# power.net
KiCad netlist of a schematic drawn in Altium Designer
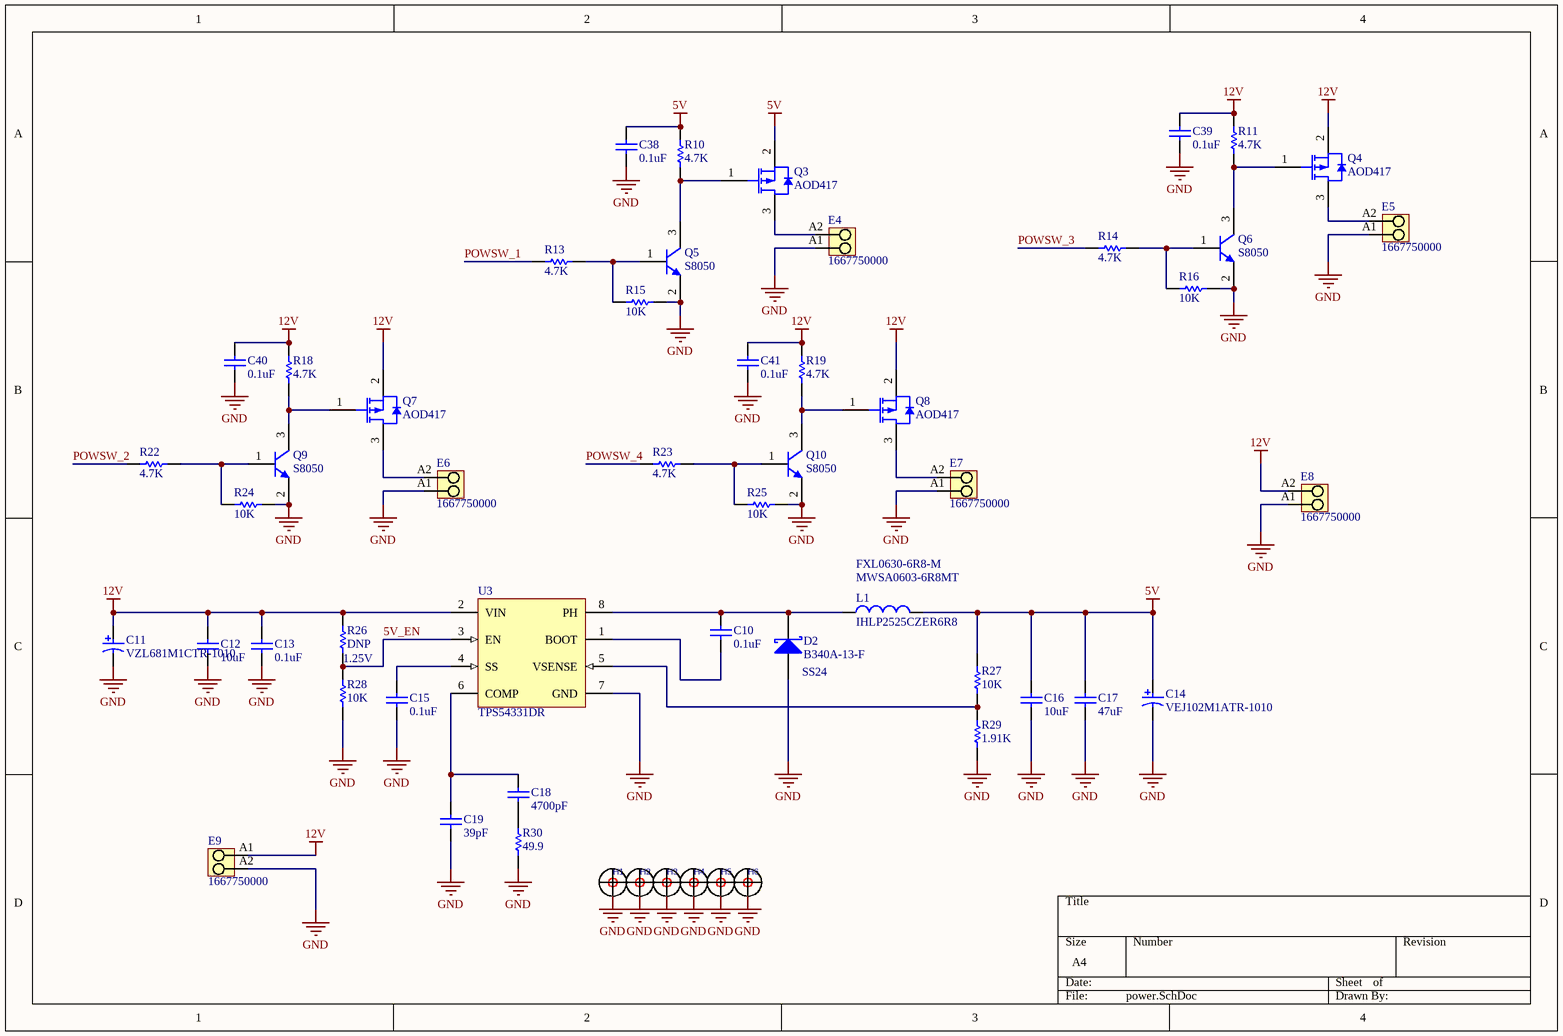
[diagram p0: power.SchDoc]

(export (version "E")
  (design (tool "Eeschema 10.0.6"))
  (components
    (comp (ref "C10")
      (value "0.1uF")
      (footprint "CAPC0603(1608)100_L")
      (description "0603 (1608 Metric) Chip Capacitor")
      (libsource (lib "Altium Content Vault") (part "CAP_5"))
    )
    (comp (ref "C11")
      (value "VZL681M1CTR-1010")
      (footprint "PNSC-SVP-F12_L")
      (description "680uF,16V,-55~105℃")
      (fields (field (name "TOLERANCE") "±20%") (field (name "MANUFACTURER") "Lelon"))
      (libsource (lib "Altium Content Vault") (part "CAP-P-2"))
    )
    (comp (ref "C12")
      (value "10uF")
      (footprint "CAPC0805(2012)145_L")
      (description "0805 (2012 Metric) Chip Capacitor")
      (libsource (lib "PCB_Project1") (part "CAP_5_1"))
    )
    (comp (ref "C13")
      (value "0.1uF")
      (footprint "CAPC0603(1608)100_L")
      (description "0603 (1608 Metric) Chip Capacitor")
      (libsource (lib "Altium Content Vault") (part "CAP_5"))
    )
    (comp (ref "C14")
      (value "VEJ102M1ATR-1010")
      (footprint "PNSC-SVP-F12_L")
      (description "1000uF,10V,-55~105℃")
      (fields (field (name "TOLERANCE") "±20%") (field (name "MANUFACTURER") "Lelon"))
      (libsource (lib "Altium Content Vault") (part "CAP-P-2"))
    )
    (comp (ref "C15")
      (value "0.1uF")
      (footprint "CAPC0603(1608)100_L")
      (description "0603 (1608 Metric) Chip Capacitor")
      (libsource (lib "Altium Content Vault") (part "CAP_5"))
    )
    (comp (ref "C16")
      (value "10uF")
      (footprint "CAPC0805(2012)145_L")
      (description "0805 (2012 Metric) Chip Capacitor")
      (libsource (lib "PCB_Project1") (part "CAP_5_1"))
    )
    (comp (ref "C17")
      (value "47uF")
      (footprint "CAPC1206(3216)150_L")
      (description "1206 (3216 Metric) Chip Capacitor")
      (libsource (lib "IC0") (part "CAP_5_3"))
    )
    (comp (ref "C18")
      (value "4700pF")
      (footprint "CAPC0603(1608)100_L")
      (description "0603 (1608 Metric) Chip Capacitor")
      (libsource (lib "Altium Content Vault") (part "CAP_5"))
    )
    (comp (ref "C19")
      (value "39pF")
      (footprint "CAPC0603(1608)100_L")
      (description "0603 (1608 Metric) Chip Capacitor")
      (libsource (lib "Altium Content Vault") (part "CAP_5"))
    )
    (comp (ref "C38")
      (value "0.1uF")
      (footprint "CAPC0603(1608)100_L")
      (description "0603 (1608 Metric) Chip Capacitor")
      (libsource (lib "Altium Content Vault") (part "CAP_5"))
    )
    (comp (ref "C39")
      (value "0.1uF")
      (footprint "CAPC0603(1608)100_L")
      (description "0603 (1608 Metric) Chip Capacitor")
      (libsource (lib "Altium Content Vault") (part "CAP_5"))
    )
    (comp (ref "C40")
      (value "0.1uF")
      (footprint "CAPC0603(1608)100_L")
      (description "0603 (1608 Metric) Chip Capacitor")
      (libsource (lib "Altium Content Vault") (part "CAP_5"))
    )
    (comp (ref "C41")
      (value "0.1uF")
      (footprint "CAPC0603(1608)100_L")
      (description "0603 (1608 Metric) Chip Capacitor")
      (libsource (lib "Altium Content Vault") (part "CAP_5"))
    )
    (comp (ref "D2")
      (value "B340A-13-F")
      (footprint "DIOD-SMA-2_V")
      (libsource (lib "Altium Content Vault") (part "DSKY-AK-2"))
    )
    (comp (ref "E4")
      (value "1667750000")
      (footprint "LM_3_5_90_02")
      (description "OMNIMATE Signal - series LM")
      (fields (field (name "MANUFACTURER") "Weidmueller"))
      (libsource (lib "Altium Content Vault") (part "Terminal_02_1x02"))
    )
    (comp (ref "E5")
      (value "1667750000")
      (footprint "LM_3_5_90_02")
      (description "OMNIMATE Signal - series LM")
      (fields (field (name "MANUFACTURER") "Weidmueller"))
      (libsource (lib "Altium Content Vault") (part "Terminal_02_1x02"))
    )
    (comp (ref "E6")
      (value "1667750000")
      (footprint "LM_3_5_90_02")
      (description "OMNIMATE Signal - series LM")
      (fields (field (name "MANUFACTURER") "Weidmueller"))
      (libsource (lib "Altium Content Vault") (part "Terminal_02_1x02"))
    )
    (comp (ref "E7")
      (value "1667750000")
      (footprint "LM_3_5_90_02")
      (description "OMNIMATE Signal - series LM")
      (fields (field (name "MANUFACTURER") "Weidmueller"))
      (libsource (lib "Altium Content Vault") (part "Terminal_02_1x02"))
    )
    (comp (ref "E8")
      (value "1667750000")
      (footprint "LM_3_5_90_02")
      (description "OMNIMATE Signal - series LM")
      (fields (field (name "MANUFACTURER") "Weidmueller"))
      (libsource (lib "Altium Content Vault") (part "Terminal_02_1x02"))
    )
    (comp (ref "E9")
      (value "1667750000")
      (footprint "LM_3_5_90_02")
      (description "OMNIMATE Signal - series LM")
      (fields (field (name "MANUFACTURER") "Weidmueller"))
      (libsource (lib "") (part "Terminal_02_1x02_1"))
    )
    (comp (ref "H1") (value "HOLE") (footprint "HOLE_Φ3_3") (libsource (lib "小车") (part "HOLE")))
    (comp (ref "H2") (value "HOLE") (footprint "HOLE_Φ3_3") (libsource (lib "小车") (part "HOLE")))
    (comp (ref "H3") (value "HOLE") (footprint "HOLE_Φ3_3") (libsource (lib "小车") (part "HOLE")))
    (comp (ref "H4") (value "HOLE") (footprint "HOLE_Φ3_3") (libsource (lib "小车") (part "HOLE")))
    (comp (ref "H5") (value "HOLE") (footprint "HOLE_Φ3_3") (libsource (lib "小车") (part "HOLE")))
    (comp (ref "H6") (value "HOLE") (footprint "HOLE_Φ3_3") (libsource (lib "小车") (part "HOLE")))
    (comp (ref "L1")
      (value "IHLP2525CZER6R8")
      (footprint "VISH-IHLP2525CZER220M11_V")
      (fields (field (name "MANUFACTURER") "Vishay") (field (name "TOLERANCE") "±20%"))
      (libsource (lib "Altium Content Vault") (part "IND-2"))
    )
    (comp (ref "Q3")
      (value "AOD417")
      (footprint "DIOD-TO252-3_V")
      (fields (field (name "MANUFACTURER") "Diodes Inc"))
      (libsource (lib "Altium Content Vault") (part "PEMOS-GSD-3"))
    )
    (comp (ref "Q4")
      (value "AOD417")
      (footprint "DIOD-TO252-3_V")
      (fields (field (name "MANUFACTURER") "Diodes Inc"))
      (libsource (lib "Altium Content Vault") (part "PEMOS-GSD-3"))
    )
    (comp (ref "Q5")
      (value "S8050")
      (footprint "KOCN-SOT23-3_L")
      (description "NPN Transistor, 0.8 A Collector Current, 3-Pin SOT23, RoHS, Tape and Reel")
      (fields (field (name "MANUFACTURER") "Koo Chin"))
      (libsource (lib "Altium Content Vault") (part "KOCN-NPN-B1E2C3-3"))
    )
    (comp (ref "Q6")
      (value "S8050")
      (footprint "KOCN-SOT23-3_L")
      (description "NPN Transistor, 0.8 A Collector Current, 3-Pin SOT23, RoHS, Tape and Reel")
      (fields (field (name "MANUFACTURER") "Koo Chin"))
      (libsource (lib "Altium Content Vault") (part "KOCN-NPN-B1E2C3-3"))
    )
    (comp (ref "Q7")
      (value "AOD417")
      (footprint "DIOD-TO252-3_V")
      (fields (field (name "MANUFACTURER") "Diodes Inc"))
      (libsource (lib "Altium Content Vault") (part "PEMOS-GSD-3"))
    )
    (comp (ref "Q8")
      (value "AOD417")
      (footprint "DIOD-TO252-3_V")
      (fields (field (name "MANUFACTURER") "Diodes Inc"))
      (libsource (lib "Altium Content Vault") (part "PEMOS-GSD-3"))
    )
    (comp (ref "Q9")
      (value "S8050")
      (footprint "KOCN-SOT23-3_L")
      (description "NPN Transistor, 0.8 A Collector Current, 3-Pin SOT23, RoHS, Tape and Reel")
      (fields (field (name "MANUFACTURER") "Koo Chin"))
      (libsource (lib "Altium Content Vault") (part "KOCN-NPN-B1E2C3-3"))
    )
    (comp (ref "Q10")
      (value "S8050")
      (footprint "KOCN-SOT23-3_L")
      (description "NPN Transistor, 0.8 A Collector Current, 3-Pin SOT23, RoHS, Tape and Reel")
      (fields (field (name "MANUFACTURER") "Koo Chin"))
      (libsource (lib "Altium Content Vault") (part "KOCN-NPN-B1E2C3-3"))
    )
    (comp (ref "R10")
      (value "4.7K")
      (footprint "RESC0603(1608)_L")
      (description "0603 (1608 Metric) Chip Resistor")
      (libsource (lib "PCB_Project1") (part "RES_3_1"))
    )
    (comp (ref "R11")
      (value "4.7K")
      (footprint "RESC0603(1608)_L")
      (description "0603 (1608 Metric) Chip Resistor")
      (libsource (lib "PCB_Project1") (part "RES_3_1"))
    )
    (comp (ref "R13")
      (value "4.7K")
      (footprint "RESC0603(1608)_L")
      (description "0603 (1608 Metric) Chip Resistor")
      (libsource (lib "PCB_Project1") (part "RES_3_1"))
    )
    (comp (ref "R14")
      (value "4.7K")
      (footprint "RESC0603(1608)_L")
      (description "0603 (1608 Metric) Chip Resistor")
      (libsource (lib "PCB_Project1") (part "RES_3_1"))
    )
    (comp (ref "R15")
      (value "10K")
      (footprint "RESC0603(1608)_L")
      (description "0603 (1608 Metric) Chip Resistor")
      (libsource (lib "PCB_Project1") (part "RES_3_1"))
    )
    (comp (ref "R16")
      (value "10K")
      (footprint "RESC0603(1608)_L")
      (description "0603 (1608 Metric) Chip Resistor")
      (libsource (lib "PCB_Project1") (part "RES_3_1"))
    )
    (comp (ref "R18")
      (value "4.7K")
      (footprint "RESC0603(1608)_L")
      (description "0603 (1608 Metric) Chip Resistor")
      (libsource (lib "PCB_Project1") (part "RES_3_1"))
    )
    (comp (ref "R19")
      (value "4.7K")
      (footprint "RESC0603(1608)_L")
      (description "0603 (1608 Metric) Chip Resistor")
      (libsource (lib "PCB_Project1") (part "RES_3_1"))
    )
    (comp (ref "R22")
      (value "4.7K")
      (footprint "RESC0603(1608)_L")
      (description "0603 (1608 Metric) Chip Resistor")
      (libsource (lib "PCB_Project1") (part "RES_3_1"))
    )
    (comp (ref "R23")
      (value "4.7K")
      (footprint "RESC0603(1608)_L")
      (description "0603 (1608 Metric) Chip Resistor")
      (libsource (lib "PCB_Project1") (part "RES_3_1"))
    )
    (comp (ref "R24")
      (value "10K")
      (footprint "RESC0603(1608)_L")
      (description "0603 (1608 Metric) Chip Resistor")
      (libsource (lib "PCB_Project1") (part "RES_3_1"))
    )
    (comp (ref "R25")
      (value "10K")
      (footprint "RESC0603(1608)_L")
      (description "0603 (1608 Metric) Chip Resistor")
      (libsource (lib "PCB_Project1") (part "RES_3_1"))
    )
    (comp (ref "R26")
      (value "DNP")
      (footprint "RESC0603(1608)_L")
      (description "0603 (1608 Metric) Chip Resistor")
      (libsource (lib "PCB_Project1") (part "RES_3_1"))
    )
    (comp (ref "R27")
      (value "10K")
      (footprint "RESC0603(1608)_L")
      (description "0603 (1608 Metric) Chip Resistor")
      (libsource (lib "PCB_Project1") (part "RES_3_1"))
    )
    (comp (ref "R28")
      (value "10K")
      (footprint "RESC0603(1608)_L")
      (description "0603 (1608 Metric) Chip Resistor")
      (libsource (lib "PCB_Project1") (part "RES_3_1"))
    )
    (comp (ref "R29")
      (value "1.91K")
      (footprint "RESC0603(1608)_L")
      (description "0603 (1608 Metric) Chip Resistor")
      (libsource (lib "PCB_Project1") (part "RES_3_1"))
    )
    (comp (ref "R30")
      (value "49.9")
      (footprint "RESC0603(1608)_L")
      (description "0603 (1608 Metric) Chip Resistor")
      (libsource (lib "PCB_Project1") (part "RES_3_1"))
    )
    (comp (ref "U3")
      (value "TPS54331DR")
      (footprint "D8_N")
      (fields (field (name "MANUFACTURER") "Texas Instruments"))
      (libsource (lib "Altium Content Vault") (part "TI-TPS54331D8"))
    )
  )
  (nets
    (net (code "1") (name "/5V_EN") (class "Default")
      (node (ref "R26") (pin "2") (pinfunction "2_2") (pintype "passive"))
      (node (ref "R28") (pin "1") (pinfunction "1_1") (pintype "passive"))
      (node (ref "U3") (pin "3") (pinfunction "EN_3") (pintype "input"))
    )
    (net (code "2") (name "/POWSW_1") (class "Default")
      (node (ref "R13") (pin "1") (pinfunction "1_1") (pintype "passive"))
    )
    (net (code "3") (name "/POWSW_2") (class "Default")
      (node (ref "R22") (pin "1") (pinfunction "1_1") (pintype "passive"))
    )
    (net (code "4") (name "/POWSW_3") (class "Default")
      (node (ref "R14") (pin "1") (pinfunction "1_1") (pintype "passive"))
    )
    (net (code "5") (name "/POWSW_4") (class "Default")
      (node (ref "R23") (pin "1") (pinfunction "1_1") (pintype "passive"))
    )
    (net (code "6") (name "5V") (class "Default")
      (node (ref "C14") (pin "1") (pinfunction "1_1") (pintype "passive"))
      (node (ref "C16") (pin "2") (pinfunction "2_2") (pintype "passive"))
      (node (ref "C17") (pin "2") (pinfunction "2_2") (pintype "passive"))
      (node (ref "C38") (pin "2") (pinfunction "2_2") (pintype "passive"))
      (node (ref "L1") (pin "2") (pinfunction "2_2") (pintype "passive"))
      (node (ref "Q3") (pin "2") (pinfunction "SOURCE_2") (pintype "passive"))
      (node (ref "R10") (pin "1") (pinfunction "1_1") (pintype "passive"))
      (node (ref "R27") (pin "1") (pinfunction "1_1") (pintype "passive"))
    )
    (net (code "7") (name "12V") (class "Default")
      (node (ref "C11") (pin "1") (pinfunction "1_1") (pintype "passive"))
      (node (ref "C12") (pin "2") (pinfunction "2_2") (pintype "passive"))
      (node (ref "C13") (pin "2") (pinfunction "2_2") (pintype "passive"))
      (node (ref "C39") (pin "2") (pinfunction "2_2") (pintype "passive"))
      (node (ref "C40") (pin "2") (pinfunction "2_2") (pintype "passive"))
      (node (ref "C41") (pin "2") (pinfunction "2_2") (pintype "passive"))
      (node (ref "E8") (pin "A2") (pinfunction "A2_A2") (pintype "passive"))
      (node (ref "E9") (pin "A1") (pinfunction "A1_A1") (pintype "passive"))
      (node (ref "Q4") (pin "2") (pinfunction "SOURCE_2") (pintype "passive"))
      (node (ref "Q7") (pin "2") (pinfunction "SOURCE_2") (pintype "passive"))
      (node (ref "Q8") (pin "2") (pinfunction "SOURCE_2") (pintype "passive"))
      (node (ref "R11") (pin "1") (pinfunction "1_1") (pintype "passive"))
      (node (ref "R18") (pin "1") (pinfunction "1_1") (pintype "passive"))
      (node (ref "R19") (pin "1") (pinfunction "1_1") (pintype "passive"))
      (node (ref "R26") (pin "1") (pinfunction "1_1") (pintype "passive"))
      (node (ref "U3") (pin "2") (pinfunction "VIN_2") (pintype "power_in"))
    )
    (net (code "8") (name "GND") (class "Default")
      (node (ref "C11") (pin "2") (pinfunction "2_2") (pintype "passive"))
      (node (ref "C12") (pin "1") (pinfunction "1_1") (pintype "passive"))
      (node (ref "C13") (pin "1") (pinfunction "1_1") (pintype "passive"))
      (node (ref "C14") (pin "2") (pinfunction "2_2") (pintype "passive"))
      (node (ref "C15") (pin "1") (pinfunction "1_1") (pintype "passive"))
      (node (ref "C16") (pin "1") (pinfunction "1_1") (pintype "passive"))
      (node (ref "C17") (pin "1") (pinfunction "1_1") (pintype "passive"))
      (node (ref "C19") (pin "1") (pinfunction "1_1") (pintype "passive"))
      (node (ref "C38") (pin "1") (pinfunction "1_1") (pintype "passive"))
      (node (ref "C39") (pin "1") (pinfunction "1_1") (pintype "passive"))
      (node (ref "C40") (pin "1") (pinfunction "1_1") (pintype "passive"))
      (node (ref "C41") (pin "1") (pinfunction "1_1") (pintype "passive"))
      (node (ref "D2") (pin "1") (pinfunction "A_1") (pintype "passive"))
      (node (ref "E4") (pin "A1") (pinfunction "A1_A1") (pintype "passive"))
      (node (ref "E5") (pin "A1") (pinfunction "A1_A1") (pintype "passive"))
      (node (ref "E6") (pin "A1") (pinfunction "A1_A1") (pintype "passive"))
      (node (ref "E7") (pin "A1") (pinfunction "A1_A1") (pintype "passive"))
      (node (ref "E8") (pin "A1") (pinfunction "A1_A1") (pintype "passive"))
      (node (ref "E9") (pin "A2") (pinfunction "A2_A2") (pintype "passive"))
      (node (ref "H1") (pin "1") (pintype "passive"))
      (node (ref "H2") (pin "1") (pintype "passive"))
      (node (ref "H3") (pin "1") (pintype "passive"))
      (node (ref "H4") (pin "1") (pintype "passive"))
      (node (ref "H5") (pin "1") (pintype "passive"))
      (node (ref "H6") (pin "1") (pintype "passive"))
      (node (ref "Q10") (pin "2") (pinfunction "EMITTER_2") (pintype "passive"))
      (node (ref "Q5") (pin "2") (pinfunction "EMITTER_2") (pintype "passive"))
      (node (ref "Q6") (pin "2") (pinfunction "EMITTER_2") (pintype "passive"))
      (node (ref "Q9") (pin "2") (pinfunction "EMITTER_2") (pintype "passive"))
      (node (ref "R15") (pin "2") (pinfunction "2_2") (pintype "passive"))
      (node (ref "R16") (pin "2") (pinfunction "2_2") (pintype "passive"))
      (node (ref "R24") (pin "2") (pinfunction "2_2") (pintype "passive"))
      (node (ref "R25") (pin "2") (pinfunction "2_2") (pintype "passive"))
      (node (ref "R28") (pin "2") (pinfunction "2_2") (pintype "passive"))
      (node (ref "R29") (pin "2") (pinfunction "2_2") (pintype "passive"))
      (node (ref "R30") (pin "2") (pinfunction "2_2") (pintype "passive"))
      (node (ref "U3") (pin "7") (pinfunction "GND_7") (pintype "power_in"))
    )
    (net (code "9") (name "Net-(C18-Pad1)") (class "Default")
      (node (ref "C18") (pin "1") (pinfunction "1_1") (pintype "passive"))
      (node (ref "R30") (pin "1") (pinfunction "1_1") (pintype "passive"))
    )
    (net (code "10") (name "Net-(D2-K)") (class "Default")
      (node (ref "C10") (pin "2") (pinfunction "2_2") (pintype "passive"))
      (node (ref "D2") (pin "2") (pinfunction "K_2") (pintype "passive"))
      (node (ref "L1") (pin "1") (pinfunction "1_1") (pintype "passive"))
      (node (ref "U3") (pin "8") (pinfunction "PH_8") (pintype "power_in"))
    )
    (net (code "11") (name "Net-(Q3-DRAIN)") (class "Default")
      (node (ref "E4") (pin "A2") (pinfunction "A2_A2") (pintype "passive"))
      (node (ref "Q3") (pin "3") (pinfunction "DRAIN_3") (pintype "passive"))
    )
    (net (code "12") (name "Net-(Q3-GATE)") (class "Default")
      (node (ref "Q3") (pin "1") (pinfunction "GATE_1") (pintype "passive"))
      (node (ref "Q5") (pin "3") (pinfunction "COLLECTOR_3") (pintype "passive"))
      (node (ref "R10") (pin "2") (pinfunction "2_2") (pintype "passive"))
    )
    (net (code "13") (name "Net-(Q4-DRAIN)") (class "Default")
      (node (ref "E5") (pin "A2") (pinfunction "A2_A2") (pintype "passive"))
      (node (ref "Q4") (pin "3") (pinfunction "DRAIN_3") (pintype "passive"))
    )
    (net (code "14") (name "Net-(Q4-GATE)") (class "Default")
      (node (ref "Q4") (pin "1") (pinfunction "GATE_1") (pintype "passive"))
      (node (ref "Q6") (pin "3") (pinfunction "COLLECTOR_3") (pintype "passive"))
      (node (ref "R11") (pin "2") (pinfunction "2_2") (pintype "passive"))
    )
    (net (code "15") (name "Net-(Q5-BASE)") (class "Default")
      (node (ref "Q5") (pin "1") (pinfunction "BASE_1") (pintype "passive"))
      (node (ref "R13") (pin "2") (pinfunction "2_2") (pintype "passive"))
      (node (ref "R15") (pin "1") (pinfunction "1_1") (pintype "passive"))
    )
    (net (code "16") (name "Net-(Q6-BASE)") (class "Default")
      (node (ref "Q6") (pin "1") (pinfunction "BASE_1") (pintype "passive"))
      (node (ref "R14") (pin "2") (pinfunction "2_2") (pintype "passive"))
      (node (ref "R16") (pin "1") (pinfunction "1_1") (pintype "passive"))
    )
    (net (code "17") (name "Net-(Q7-DRAIN)") (class "Default")
      (node (ref "E6") (pin "A2") (pinfunction "A2_A2") (pintype "passive"))
      (node (ref "Q7") (pin "3") (pinfunction "DRAIN_3") (pintype "passive"))
    )
    (net (code "18") (name "Net-(Q7-GATE)") (class "Default")
      (node (ref "Q7") (pin "1") (pinfunction "GATE_1") (pintype "passive"))
      (node (ref "Q9") (pin "3") (pinfunction "COLLECTOR_3") (pintype "passive"))
      (node (ref "R18") (pin "2") (pinfunction "2_2") (pintype "passive"))
    )
    (net (code "19") (name "Net-(Q8-DRAIN)") (class "Default")
      (node (ref "E7") (pin "A2") (pinfunction "A2_A2") (pintype "passive"))
      (node (ref "Q8") (pin "3") (pinfunction "DRAIN_3") (pintype "passive"))
    )
    (net (code "20") (name "Net-(Q9-BASE)") (class "Default")
      (node (ref "Q9") (pin "1") (pinfunction "BASE_1") (pintype "passive"))
      (node (ref "R22") (pin "2") (pinfunction "2_2") (pintype "passive"))
      (node (ref "R24") (pin "1") (pinfunction "1_1") (pintype "passive"))
    )
    (net (code "21") (name "Net-(Q10-BASE)") (class "Default")
      (node (ref "Q10") (pin "1") (pinfunction "BASE_1") (pintype "passive"))
      (node (ref "R23") (pin "2") (pinfunction "2_2") (pintype "passive"))
      (node (ref "R25") (pin "1") (pinfunction "1_1") (pintype "passive"))
    )
    (net (code "22") (name "Net-(Q10-COLLECTOR)") (class "Default")
      (node (ref "Q10") (pin "3") (pinfunction "COLLECTOR_3") (pintype "passive"))
      (node (ref "Q8") (pin "1") (pinfunction "GATE_1") (pintype "passive"))
      (node (ref "R19") (pin "2") (pinfunction "2_2") (pintype "passive"))
    )
    (net (code "23") (name "Net-(U3-BOOT)") (class "Default")
      (node (ref "C10") (pin "1") (pinfunction "1_1") (pintype "passive"))
      (node (ref "U3") (pin "1") (pinfunction "BOOT_1") (pintype "passive"))
    )
    (net (code "24") (name "Net-(U3-COMP)") (class "Default")
      (node (ref "C18") (pin "2") (pinfunction "2_2") (pintype "passive"))
      (node (ref "C19") (pin "2") (pinfunction "2_2") (pintype "passive"))
      (node (ref "U3") (pin "6") (pinfunction "COMP_6") (pintype "passive"))
    )
    (net (code "25") (name "Net-(U3-SS)") (class "Default")
      (node (ref "C15") (pin "2") (pinfunction "2_2") (pintype "passive"))
      (node (ref "U3") (pin "4") (pinfunction "SS_4") (pintype "input"))
    )
    (net (code "26") (name "Net-(U3-VSENSE)") (class "Default")
      (node (ref "R27") (pin "2") (pinfunction "2_2") (pintype "passive"))
      (node (ref "R29") (pin "1") (pinfunction "1_1") (pintype "passive"))
      (node (ref "U3") (pin "5") (pinfunction "VSENSE_5") (pintype "input"))
    )
  )
)
